# sch.net
KiCad netlist of a schematic drawn in Altium Designer
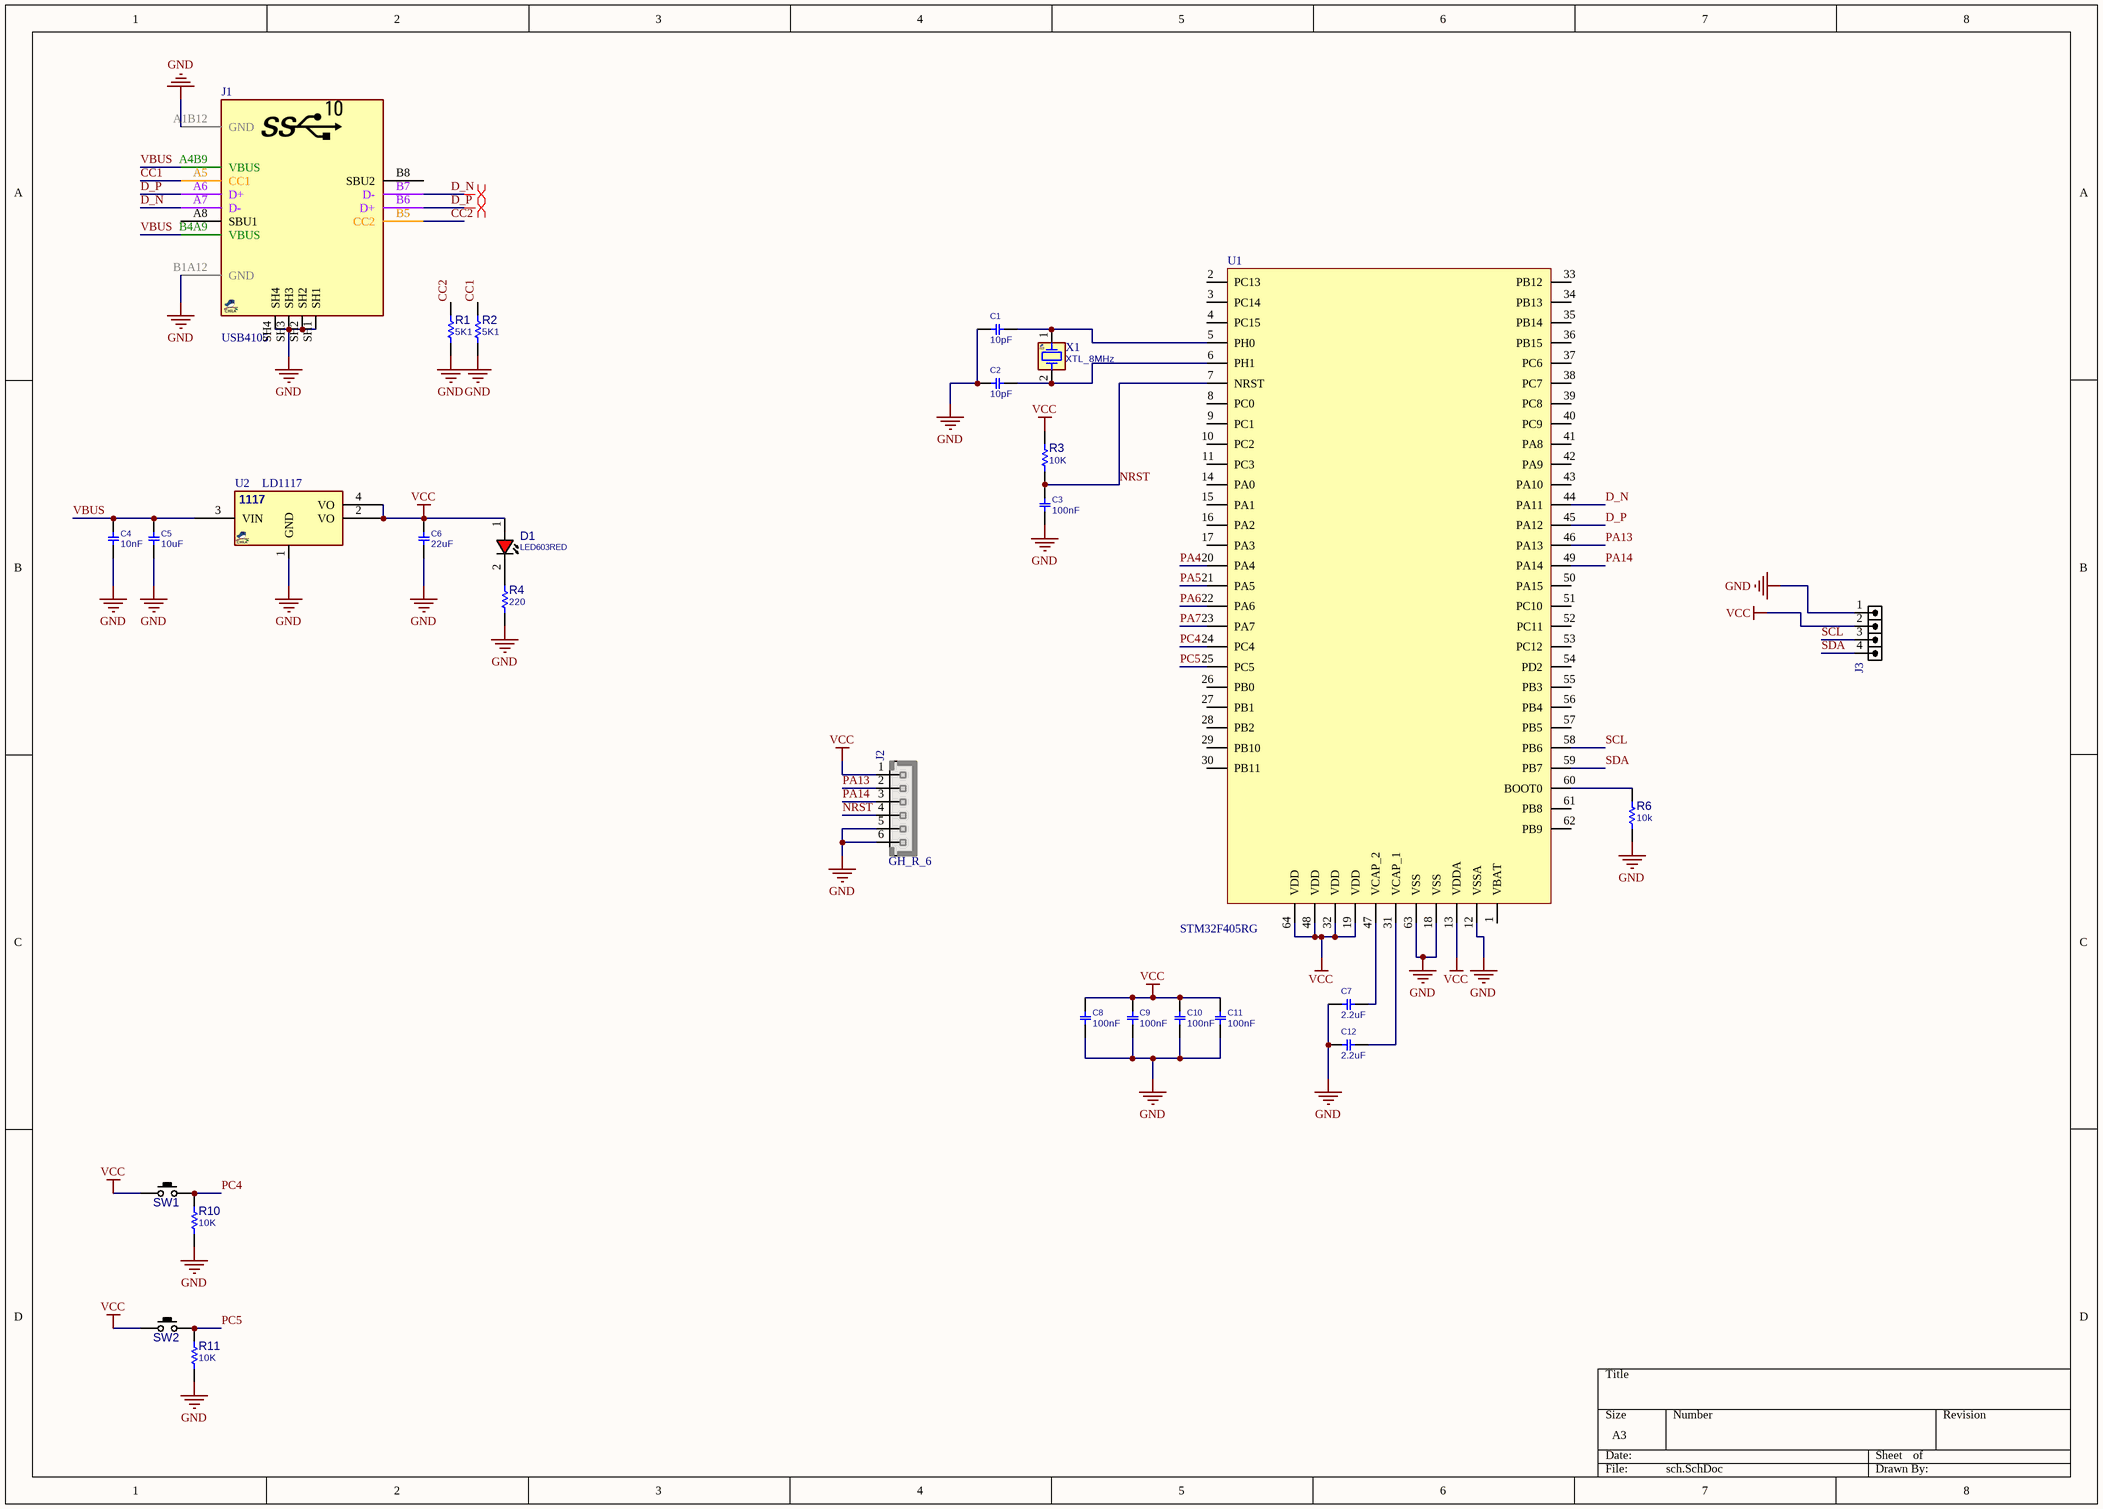
[diagram p0: sch.SchDoc]

(export (version "E")
  (design (tool "Eeschema 10.0.6"))
  (components
    (comp (ref "C1")
      (value "10pF")
      (footprint "C0603")
      (description "CAP, MLCC")
      (fields (field (name "MANF_P#") "MANF_PART#"))
      (libsource (lib "passive_smd") (part "CAP_SMD_MLCC_0603"))
    )
    (comp (ref "C2")
      (value "10pF")
      (footprint "C0603")
      (description "CAP, MLCC")
      (fields (field (name "MANF_P#") "MANF_PART#"))
      (libsource (lib "passive_smd") (part "CAP_SMD_MLCC_0603"))
    )
    (comp (ref "C3")
      (value "100nF")
      (footprint "C0603")
      (description "CAP, MLCC")
      (fields (field (name "MANF_P#") "MANF_PART#"))
      (libsource (lib "passive_smd") (part "CAP_SMD_MLCC_0603"))
    )
    (comp (ref "C4")
      (value "10nF")
      (footprint "C0603")
      (description "CAP, MLCC")
      (fields (field (name "MANF_P#") "MANF_PART#"))
      (libsource (lib "passive_smd") (part "CAP_SMD_MLCC_0603"))
    )
    (comp (ref "C5")
      (value "10uF")
      (footprint "C0603")
      (description "CAP, MLCC")
      (fields (field (name "MANF_P#") "MANF_PART#"))
      (libsource (lib "passive_smd") (part "CAP_SMD_MLCC_0603"))
    )
    (comp (ref "C6")
      (value "22uF")
      (footprint "C0603")
      (description "CAP, MLCC")
      (fields (field (name "MANF_P#") "MANF_PART#"))
      (libsource (lib "passive_smd") (part "CAP_SMD_MLCC_0603"))
    )
    (comp (ref "C7")
      (value "2.2uF")
      (footprint "C0603")
      (description "CAP, MLCC")
      (fields (field (name "MANF_P#") "MANF_PART#"))
      (libsource (lib "passive_smd") (part "CAP_SMD_MLCC_0603"))
    )
    (comp (ref "C8")
      (value "100nF")
      (footprint "C0603")
      (description "CAP, MLCC")
      (fields (field (name "MANF_P#") "MANF_PART#"))
      (libsource (lib "passive_smd") (part "CAP_SMD_MLCC_0603"))
    )
    (comp (ref "C9")
      (value "100nF")
      (footprint "C0603")
      (description "CAP, MLCC")
      (fields (field (name "MANF_P#") "MANF_PART#"))
      (libsource (lib "passive_smd") (part "CAP_SMD_MLCC_0603"))
    )
    (comp (ref "C10")
      (value "100nF")
      (footprint "C0603")
      (description "CAP, MLCC")
      (fields (field (name "MANF_P#") "MANF_PART#"))
      (libsource (lib "passive_smd") (part "CAP_SMD_MLCC_0603"))
    )
    (comp (ref "C11")
      (value "100nF")
      (footprint "C0603")
      (description "CAP, MLCC")
      (fields (field (name "MANF_P#") "MANF_PART#"))
      (libsource (lib "passive_smd") (part "CAP_SMD_MLCC_0603"))
    )
    (comp (ref "C12")
      (value "2.2uF")
      (footprint "C0603")
      (description "CAP, MLCC")
      (fields (field (name "MANF_P#") "MANF_PART#"))
      (libsource (lib "passive_smd") (part "CAP_SMD_MLCC_0603"))
    )
    (comp (ref "D1")
      (value "LED603RED")
      (footprint "LED0603RED")
      (description "LED, SMD, 0603, RED")
      (fields (field (name "MANF") "MANF") (field (name "MANF_P#") "MANF_PART#"))
      (libsource (lib "led(diode)") (part "LED_SMD_0603_RED"))
    )
    (comp (ref "J1")
      (value "USB4105")
      (footprint "USBC_SMD_16_USB4105")
      (description "CONN, USB, Type C, USB 2.0, Right-Angle, SMD")
      (fields (field (name "MANF") "GCT") (field (name "MANF_P#") "USB4105-GF-A"))
      (libsource (lib "conn_usbc") (part "CONN_USBC_SMD_16_USB4105"))
    )
    (comp (ref "J2")
      (value "GH_R_6")
      (footprint "GH_R_6")
      (description "JST GH Series, pitch: 1.25mm, 1.0A/50v")
      (fields (field (name "MANF") "JST"))
      (libsource (lib "conn_wire2board") (part "GH_R_6"))
    )
    (comp (ref "J3")
      (value "HDR1X4")
      (footprint "HDRMINI_M_1X4")
      (description "CONN, HEADER, Male, pitch: 1.27mm, 4POS")
      (libsource (lib "conn_header_1.27mm_st") (part "HDRMINI_M_1X4"))
    )
    (comp (ref "R1")
      (value "5K1")
      (footprint "R0603")
      (description "RESISTOR, SMD")
      (libsource (lib "passive_smd") (part "RES_SMD_0603"))
    )
    (comp (ref "R2")
      (value "5K1")
      (footprint "R0603")
      (description "RESISTOR, SMD")
      (libsource (lib "passive_smd") (part "RES_SMD_0603"))
    )
    (comp (ref "R3")
      (value "10K")
      (footprint "R0603")
      (description "RESISTOR, SMD")
      (libsource (lib "passive_smd") (part "RES_SMD_0603"))
    )
    (comp (ref "R4")
      (value "220")
      (footprint "R0603")
      (description "RESISTOR, SMD")
      (libsource (lib "passive_smd") (part "RES_SMD_0603"))
    )
    (comp (ref "R6")
      (value "10k")
      (footprint "R0603")
      (description "RESISTOR, SMD")
      (libsource (lib "passive_smd") (part "RES_SMD_0603"))
    )
    (comp (ref "R10")
      (value "10K")
      (footprint "R0603")
      (description "RESISTOR, SMD")
      (libsource (lib "passive_smd") (part "RES_SMD_0603"))
    )
    (comp (ref "R11")
      (value "10K")
      (footprint "R0603")
      (description "RESISTOR, SMD")
      (libsource (lib "passive_smd") (part "RES_SMD_0603"))
    )
    (comp (ref "SW1")
      (value "PUSHBUTTON")
      (footprint "SWPBT_SPST_R_6X6X6")
      (description "SWITCH, PUSH BUTTON, TACTILE, THD, SPST, 6X6X6mm RIGHT")
      (fields (field (name "MANF") "ALPS") (field (name "MANF_P#") "SKHHLUA010"))
      (libsource (lib "switch_tact_PUSHB") (part "SWPBT_SPST_R_6X6X6_SKHHLUA010"))
    )
    (comp (ref "SW2")
      (value "PUSHBUTTON")
      (footprint "SWPBT_SPST_R_6X6X6")
      (description "SWITCH, PUSH BUTTON, TACTILE, THD, SPST, 6X6X6mm RIGHT")
      (fields (field (name "MANF") "ALPS") (field (name "MANF_P#") "SKHHLUA010"))
      (libsource (lib "switch_tact_PUSHB") (part "SWPBT_SPST_R_6X6X6_SKHHLUA010"))
    )
    (comp (ref "U1")
      (value "STM32F405RG")
      (footprint "QFG50_64")
      (libsource (lib "Schlib1") (part "STM32F405RG"))
    )
    (comp (ref "U2")
      (value "LD1117")
      (footprint "SOT223_4")
      (description "REG, Linear, LDO1V, 0.8A, SOT-223")
      (fields
        (field (name "MANF_P#") "LD1117, LM1117, AMS1117, TLV1117, REG1117, NCP1117, LT1117, SPX1117")
        (field (name "MANF") "TI, ON, ST")
      )
      (libsource (lib "pwr_reg_linear_1117") (part "VREG_1117_SOT223"))
    )
    (comp (ref "X1")
      (value "XTL_8MHz")
      (footprint "XTL_2_11X5")
      (description "Crystal MOST POPULAR ABL HC49 PACKAGE")
      (fields (field (name "MANF") "ABRACON") (field (name "MANF_P#") "ABLS-8.000MHZ-B4-T"))
      (libsource (lib "crystal") (part "XTL_2_HC49_8MHz_SMD"))
    )
  )
  (nets
    (net (code "1") (name "/CC1") (class "Default")
      (node (ref "J1") (pin "A5") (pinfunction "CC1_A5") (pintype "passive"))
      (node (ref "R2") (pin "2") (pinfunction "2_2") (pintype "passive"))
    )
    (net (code "2") (name "/CC2") (class "Default")
      (node (ref "J1") (pin "B5") (pinfunction "CC2_B5") (pintype "passive"))
      (node (ref "R1") (pin "2") (pinfunction "2_2") (pintype "passive"))
    )
    (net (code "3") (name "/D_N") (class "Default")
      (node (ref "J1") (pin "A7") (pinfunction "D-_A7") (pintype "passive"))
      (node (ref "J1") (pin "B7") (pinfunction "D-_B7") (pintype "passive"))
      (node (ref "U1") (pin "44") (pinfunction "PA11_44") (pintype "passive"))
    )
    (net (code "4") (name "/D_P") (class "Default")
      (node (ref "J1") (pin "A6") (pinfunction "D+_A6") (pintype "passive"))
      (node (ref "J1") (pin "B6") (pinfunction "D+_B6") (pintype "passive"))
      (node (ref "U1") (pin "45") (pinfunction "PA12_45") (pintype "passive"))
    )
    (net (code "5") (name "/NRST") (class "Default")
      (node (ref "C3") (pin "2") (pinfunction "2_2") (pintype "passive"))
      (node (ref "J2") (pin "4") (pinfunction "4_4") (pintype "passive"))
      (node (ref "R3") (pin "1") (pinfunction "1_1") (pintype "passive"))
      (node (ref "U1") (pin "7") (pinfunction "NRST_7") (pintype "passive"))
    )
    (net (code "6") (name "/PA4") (class "Default")
      (node (ref "U1") (pin "20") (pinfunction "PA4_20") (pintype "passive"))
    )
    (net (code "7") (name "/PA5") (class "Default")
      (node (ref "U1") (pin "21") (pinfunction "PA5_21") (pintype "passive"))
    )
    (net (code "8") (name "/PA6") (class "Default")
      (node (ref "U1") (pin "22") (pinfunction "PA6_22") (pintype "passive"))
    )
    (net (code "9") (name "/PA7") (class "Default")
      (node (ref "U1") (pin "23") (pinfunction "PA7_23") (pintype "passive"))
    )
    (net (code "10") (name "/PA13") (class "Default")
      (node (ref "J2") (pin "2") (pinfunction "2_2") (pintype "passive"))
      (node (ref "U1") (pin "46") (pinfunction "PA13_46") (pintype "passive"))
    )
    (net (code "11") (name "/PA14") (class "Default")
      (node (ref "J2") (pin "3") (pinfunction "3_3") (pintype "passive"))
      (node (ref "U1") (pin "49") (pinfunction "PA14_49") (pintype "passive"))
    )
    (net (code "12") (name "/PC4") (class "Default")
      (node (ref "R10") (pin "2") (pinfunction "2_2") (pintype "passive"))
      (node (ref "SW1") (pin "2") (pinfunction "2_2") (pintype "passive"))
      (node (ref "U1") (pin "24") (pinfunction "PC4_24") (pintype "passive"))
    )
    (net (code "13") (name "/PC5") (class "Default")
      (node (ref "R11") (pin "2") (pinfunction "2_2") (pintype "passive"))
      (node (ref "SW2") (pin "2") (pinfunction "2_2") (pintype "passive"))
      (node (ref "U1") (pin "25") (pinfunction "PC5_25") (pintype "passive"))
    )
    (net (code "14") (name "/SCL") (class "Default")
      (node (ref "J3") (pin "3") (pinfunction "3_3") (pintype "passive"))
      (node (ref "U1") (pin "58") (pinfunction "PB6_58") (pintype "passive"))
    )
    (net (code "15") (name "/SDA") (class "Default")
      (node (ref "J3") (pin "4") (pinfunction "4_4") (pintype "passive"))
      (node (ref "U1") (pin "59") (pinfunction "PB7_59") (pintype "passive"))
    )
    (net (code "16") (name "/VBUS") (class "Default")
      (node (ref "C4") (pin "2") (pinfunction "2_2") (pintype "passive"))
      (node (ref "C5") (pin "2") (pinfunction "2_2") (pintype "passive"))
      (node (ref "J1") (pin "A4B9") (pinfunction "VBUS_A4B9") (pintype "passive"))
      (node (ref "J1") (pin "B4A9") (pinfunction "VBUS_B4A9") (pintype "passive"))
      (node (ref "U2") (pin "3") (pinfunction "VIN_3") (pintype "passive"))
    )
    (net (code "17") (name "GND") (class "Default")
      (node (ref "C1") (pin "1") (pinfunction "1_1") (pintype "passive"))
      (node (ref "C10") (pin "1") (pinfunction "1_1") (pintype "passive"))
      (node (ref "C11") (pin "1") (pinfunction "1_1") (pintype "passive"))
      (node (ref "C12") (pin "1") (pinfunction "1_1") (pintype "passive"))
      (node (ref "C2") (pin "1") (pinfunction "1_1") (pintype "passive"))
      (node (ref "C3") (pin "1") (pinfunction "1_1") (pintype "passive"))
      (node (ref "C4") (pin "1") (pinfunction "1_1") (pintype "passive"))
      (node (ref "C5") (pin "1") (pinfunction "1_1") (pintype "passive"))
      (node (ref "C6") (pin "1") (pinfunction "1_1") (pintype "passive"))
      (node (ref "C7") (pin "1") (pinfunction "1_1") (pintype "passive"))
      (node (ref "C8") (pin "1") (pinfunction "1_1") (pintype "passive"))
      (node (ref "C9") (pin "1") (pinfunction "1_1") (pintype "passive"))
      (node (ref "J1") (pin "A1B12") (pinfunction "GND_A1B12") (pintype "passive"))
      (node (ref "J1") (pin "B1A12") (pinfunction "GND_B1A12") (pintype "passive"))
      (node (ref "J1") (pin "SH1") (pinfunction "SH1_SH1") (pintype "passive"))
      (node (ref "J1") (pin "SH2") (pinfunction "SH2_SH2") (pintype "passive"))
      (node (ref "J1") (pin "SH3") (pinfunction "SH3_SH3") (pintype "passive"))
      (node (ref "J1") (pin "SH4") (pinfunction "SH4_SH4") (pintype "passive"))
      (node (ref "J2") (pin "5") (pinfunction "5_5") (pintype "passive"))
      (node (ref "J2") (pin "6") (pinfunction "6_6") (pintype "passive"))
      (node (ref "J3") (pin "1") (pinfunction "1_1") (pintype "passive"))
      (node (ref "R1") (pin "1") (pinfunction "1_1") (pintype "passive"))
      (node (ref "R10") (pin "1") (pinfunction "1_1") (pintype "passive"))
      (node (ref "R11") (pin "1") (pinfunction "1_1") (pintype "passive"))
      (node (ref "R2") (pin "1") (pinfunction "1_1") (pintype "passive"))
      (node (ref "R4") (pin "1") (pinfunction "1_1") (pintype "passive"))
      (node (ref "R6") (pin "1") (pinfunction "1_1") (pintype "passive"))
      (node (ref "U1") (pin "12") (pinfunction "VSSA_12") (pintype "passive"))
      (node (ref "U1") (pin "18") (pinfunction "VSS_18") (pintype "passive"))
      (node (ref "U1") (pin "63") (pinfunction "VSS_63") (pintype "passive"))
      (node (ref "U2") (pin "1") (pinfunction "GND_1") (pintype "passive"))
    )
    (net (code "18") (name "Net-(D1-CATHODE)") (class "Default")
      (node (ref "D1") (pin "2") (pinfunction "CATHODE_2") (pintype "passive"))
      (node (ref "R4") (pin "2") (pinfunction "2_2") (pintype "passive"))
    )
    (net (code "19") (name "Net-(U1-BOOT0)") (class "Default")
      (node (ref "R6") (pin "2") (pinfunction "2_2") (pintype "passive"))
      (node (ref "U1") (pin "60") (pinfunction "BOOT0_60") (pintype "passive"))
    )
    (net (code "20") (name "Net-(U1-PH0)") (class "Default")
      (node (ref "C1") (pin "2") (pinfunction "2_2") (pintype "passive"))
      (node (ref "U1") (pin "5") (pinfunction "PH0_5") (pintype "passive"))
      (node (ref "X1") (pin "1") (pinfunction "OSC1_1") (pintype "passive"))
    )
    (net (code "21") (name "Net-(U1-PH1)") (class "Default")
      (node (ref "C2") (pin "2") (pinfunction "2_2") (pintype "passive"))
      (node (ref "U1") (pin "6") (pinfunction "PH1_6") (pintype "passive"))
      (node (ref "X1") (pin "2") (pinfunction "OSC2_2") (pintype "passive"))
    )
    (net (code "22") (name "Net-(U1-VCAP_1)") (class "Default")
      (node (ref "C12") (pin "2") (pinfunction "2_2") (pintype "passive"))
      (node (ref "U1") (pin "31") (pinfunction "VCAP_1_31") (pintype "passive"))
    )
    (net (code "23") (name "Net-(U1-VCAP_2)") (class "Default")
      (node (ref "C7") (pin "2") (pinfunction "2_2") (pintype "passive"))
      (node (ref "U1") (pin "47") (pinfunction "VCAP_2_47") (pintype "passive"))
    )
    (net (code "24") (name "VCC") (class "Default")
      (node (ref "C10") (pin "2") (pinfunction "2_2") (pintype "passive"))
      (node (ref "C11") (pin "2") (pinfunction "2_2") (pintype "passive"))
      (node (ref "C6") (pin "2") (pinfunction "2_2") (pintype "passive"))
      (node (ref "C8") (pin "2") (pinfunction "2_2") (pintype "passive"))
      (node (ref "C9") (pin "2") (pinfunction "2_2") (pintype "passive"))
      (node (ref "D1") (pin "1") (pinfunction "ANODE_1") (pintype "passive"))
      (node (ref "J2") (pin "1") (pinfunction "1_1") (pintype "passive"))
      (node (ref "J3") (pin "2") (pinfunction "2_2") (pintype "passive"))
      (node (ref "R3") (pin "2") (pinfunction "2_2") (pintype "passive"))
      (node (ref "SW1") (pin "1") (pinfunction "1_1") (pintype "passive"))
      (node (ref "SW2") (pin "1") (pinfunction "1_1") (pintype "passive"))
      (node (ref "U1") (pin "13") (pinfunction "VDDA_13") (pintype "passive"))
      (node (ref "U1") (pin "19") (pinfunction "VDD_19") (pintype "passive"))
      (node (ref "U1") (pin "32") (pinfunction "VDD_32") (pintype "passive"))
      (node (ref "U1") (pin "48") (pinfunction "VDD_48") (pintype "passive"))
      (node (ref "U1") (pin "64") (pinfunction "VDD_64") (pintype "passive"))
      (node (ref "U2") (pin "2") (pinfunction "VO_2") (pintype "passive"))
      (node (ref "U2") (pin "4") (pinfunction "VO_4") (pintype "passive"))
    )
    (net (code "25") (name "unconnected-(J1-SBU1-PadA8)") (class "Default")
      (node (ref "J1") (pin "A8") (pinfunction "SBU1_A8") (pintype "passive"))
    )
    (net (code "26") (name "unconnected-(J1-SBU2-PadB8)") (class "Default")
      (node (ref "J1") (pin "B8") (pinfunction "SBU2_B8") (pintype "passive"))
    )
    (net (code "27") (name "unconnected-(U1-PA0-Pad14)") (class "Default")
      (node (ref "U1") (pin "14") (pinfunction "PA0_14") (pintype "passive"))
    )
    (net (code "28") (name "unconnected-(U1-PA1-Pad15)") (class "Default")
      (node (ref "U1") (pin "15") (pinfunction "PA1_15") (pintype "passive"))
    )
    (net (code "29") (name "unconnected-(U1-PA2-Pad16)") (class "Default")
      (node (ref "U1") (pin "16") (pinfunction "PA2_16") (pintype "passive"))
    )
    (net (code "30") (name "unconnected-(U1-PA3-Pad17)") (class "Default")
      (node (ref "U1") (pin "17") (pinfunction "PA3_17") (pintype "passive"))
    )
    (net (code "31") (name "unconnected-(U1-PA8-Pad41)") (class "Default")
      (node (ref "U1") (pin "41") (pinfunction "PA8_41") (pintype "passive"))
    )
    (net (code "32") (name "unconnected-(U1-PA9-Pad42)") (class "Default")
      (node (ref "U1") (pin "42") (pinfunction "PA9_42") (pintype "passive"))
    )
    (net (code "33") (name "unconnected-(U1-PA10-Pad43)") (class "Default")
      (node (ref "U1") (pin "43") (pinfunction "PA10_43") (pintype "passive"))
    )
    (net (code "34") (name "unconnected-(U1-PA15-Pad50)") (class "Default")
      (node (ref "U1") (pin "50") (pinfunction "PA15_50") (pintype "passive"))
    )
    (net (code "35") (name "unconnected-(U1-PB0-Pad26)") (class "Default")
      (node (ref "U1") (pin "26") (pinfunction "PB0_26") (pintype "passive"))
    )
    (net (code "36") (name "unconnected-(U1-PB1-Pad27)") (class "Default")
      (node (ref "U1") (pin "27") (pinfunction "PB1_27") (pintype "passive"))
    )
    (net (code "37") (name "unconnected-(U1-PB2-Pad28)") (class "Default")
      (node (ref "U1") (pin "28") (pinfunction "PB2_28") (pintype "passive"))
    )
    (net (code "38") (name "unconnected-(U1-PB3-Pad55)") (class "Default")
      (node (ref "U1") (pin "55") (pinfunction "PB3_55") (pintype "passive"))
    )
    (net (code "39") (name "unconnected-(U1-PB4-Pad56)") (class "Default")
      (node (ref "U1") (pin "56") (pinfunction "PB4_56") (pintype "passive"))
    )
    (net (code "40") (name "unconnected-(U1-PB5-Pad57)") (class "Default")
      (node (ref "U1") (pin "57") (pinfunction "PB5_57") (pintype "passive"))
    )
    (net (code "41") (name "unconnected-(U1-PB8-Pad61)") (class "Default")
      (node (ref "U1") (pin "61") (pinfunction "PB8_61") (pintype "passive"))
    )
    (net (code "42") (name "unconnected-(U1-PB9-Pad62)") (class "Default")
      (node (ref "U1") (pin "62") (pinfunction "PB9_62") (pintype "passive"))
    )
    (net (code "43") (name "unconnected-(U1-PB10-Pad29)") (class "Default")
      (node (ref "U1") (pin "29") (pinfunction "PB10_29") (pintype "passive"))
    )
    (net (code "44") (name "unconnected-(U1-PB11-Pad30)") (class "Default")
      (node (ref "U1") (pin "30") (pinfunction "PB11_30") (pintype "passive"))
    )
    (net (code "45") (name "unconnected-(U1-PB12-Pad33)") (class "Default")
      (node (ref "U1") (pin "33") (pinfunction "PB12_33") (pintype "passive"))
    )
    (net (code "46") (name "unconnected-(U1-PB13-Pad34)") (class "Default")
      (node (ref "U1") (pin "34") (pinfunction "PB13_34") (pintype "passive"))
    )
    (net (code "47") (name "unconnected-(U1-PB14-Pad35)") (class "Default")
      (node (ref "U1") (pin "35") (pinfunction "PB14_35") (pintype "passive"))
    )
    (net (code "48") (name "unconnected-(U1-PB15-Pad36)") (class "Default")
      (node (ref "U1") (pin "36") (pinfunction "PB15_36") (pintype "passive"))
    )
    (net (code "49") (name "unconnected-(U1-PC0-Pad8)") (class "Default")
      (node (ref "U1") (pin "8") (pinfunction "PC0_8") (pintype "passive"))
    )
    (net (code "50") (name "unconnected-(U1-PC1-Pad9)") (class "Default")
      (node (ref "U1") (pin "9") (pinfunction "PC1_9") (pintype "passive"))
    )
    (net (code "51") (name "unconnected-(U1-PC2-Pad10)") (class "Default")
      (node (ref "U1") (pin "10") (pinfunction "PC2_10") (pintype "passive"))
    )
    (net (code "52") (name "unconnected-(U1-PC3-Pad11)") (class "Default")
      (node (ref "U1") (pin "11") (pinfunction "PC3_11") (pintype "passive"))
    )
    (net (code "53") (name "unconnected-(U1-PC6-Pad37)") (class "Default")
      (node (ref "U1") (pin "37") (pinfunction "PC6_37") (pintype "passive"))
    )
    (net (code "54") (name "unconnected-(U1-PC7-Pad38)") (class "Default")
      (node (ref "U1") (pin "38") (pinfunction "PC7_38") (pintype "passive"))
    )
    (net (code "55") (name "unconnected-(U1-PC8-Pad39)") (class "Default")
      (node (ref "U1") (pin "39") (pinfunction "PC8_39") (pintype "passive"))
    )
    (net (code "56") (name "unconnected-(U1-PC9-Pad40)") (class "Default")
      (node (ref "U1") (pin "40") (pinfunction "PC9_40") (pintype "passive"))
    )
    (net (code "57") (name "unconnected-(U1-PC10-Pad51)") (class "Default")
      (node (ref "U1") (pin "51") (pinfunction "PC10_51") (pintype "passive"))
    )
    (net (code "58") (name "unconnected-(U1-PC11-Pad52)") (class "Default")
      (node (ref "U1") (pin "52") (pinfunction "PC11_52") (pintype "passive"))
    )
    (net (code "59") (name "unconnected-(U1-PC12-Pad53)") (class "Default")
      (node (ref "U1") (pin "53") (pinfunction "PC12_53") (pintype "passive"))
    )
    (net (code "60") (name "unconnected-(U1-PC13-Pad2)") (class "Default")
      (node (ref "U1") (pin "2") (pinfunction "PC13_2") (pintype "passive"))
    )
    (net (code "61") (name "unconnected-(U1-PC14-Pad3)") (class "Default")
      (node (ref "U1") (pin "3") (pinfunction "PC14_3") (pintype "passive"))
    )
    (net (code "62") (name "unconnected-(U1-PC15-Pad4)") (class "Default")
      (node (ref "U1") (pin "4") (pinfunction "PC15_4") (pintype "passive"))
    )
    (net (code "63") (name "unconnected-(U1-PD2-Pad54)") (class "Default")
      (node (ref "U1") (pin "54") (pinfunction "PD2_54") (pintype "passive"))
    )
    (net (code "64") (name "unconnected-(U1-VBAT-Pad1)") (class "Default")
      (node (ref "U1") (pin "1") (pinfunction "VBAT_1") (pintype "passive"))
    )
  )
)
